# 01_Top.net
KiCad netlist of a schematic drawn in Altium Designer
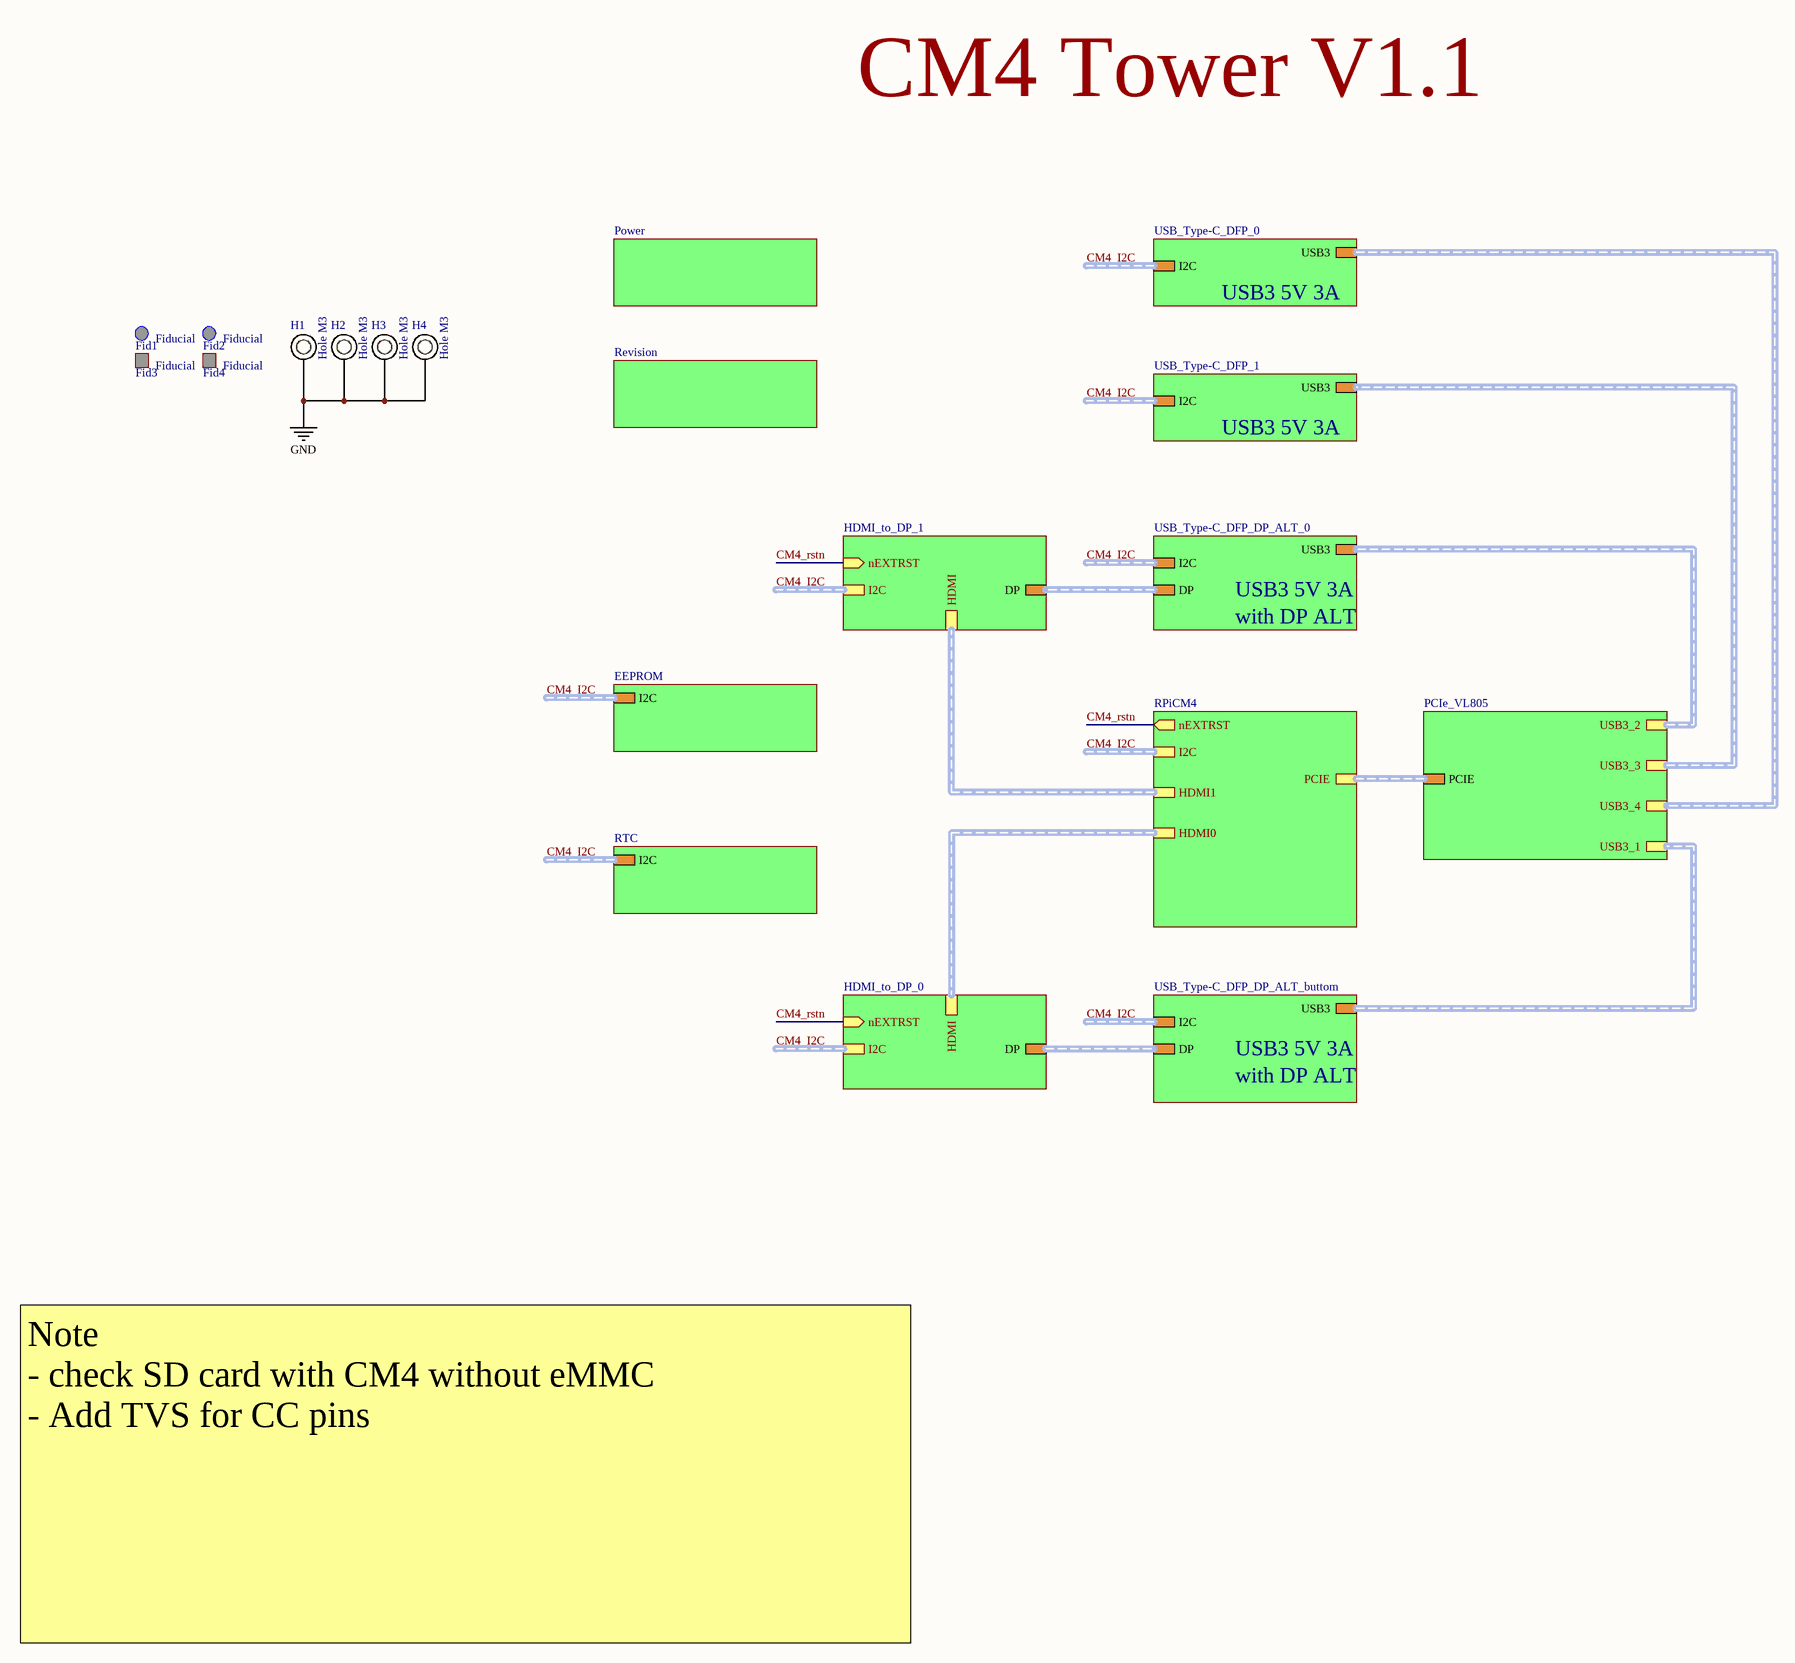
[diagram p0: 01_Top.SchDoc]

(export (version "E")
  (design (tool "Eeschema 10.0.6"))
  (components
    (comp (ref "Fid1")
      (value "Fiducial")
      (footprint "FidR_1.0mm")
      (description "Fiducial Round 1mm")
      (fields (field (name "REFVAL") "Fiducial") (field (name "PART NUMBER") "ME0011"))
      (libsource (lib "GTS_Database") (part "FidR_1.0mm"))
    )
    (comp (ref "Fid2")
      (value "Fiducial")
      (footprint "FidR_1.0mm")
      (description "Fiducial Round 1mm")
      (fields (field (name "REFVAL") "Fiducial") (field (name "PART NUMBER") "ME0011"))
      (libsource (lib "GTS_Database") (part "FidR_1.0mm"))
    )
    (comp (ref "Fid3")
      (value "Fiducial")
      (footprint "FidS_1.0mm")
      (description "Fiducial Sqaure 1mm")
      (fields (field (name "REFVAL") "Fiducial") (field (name "PART NUMBER") "ME0012"))
      (libsource (lib "GTS_Database") (part "FidS_1.0mm"))
    )
    (comp (ref "Fid4")
      (value "Fiducial")
      (footprint "FidS_1.0mm")
      (description "Fiducial Sqaure 1mm")
      (fields (field (name "REFVAL") "Fiducial") (field (name "PART NUMBER") "ME0012"))
      (libsource (lib "GTS_Database") (part "FidS_1.0mm"))
    )
    (comp (ref "H1")
      (value "Hole M3")
      (footprint "HOLE_M3")
      (description "Mounting Hole M3")
      (fields (field (name "REFVAL") "Hole M3") (field (name "PART NUMBER") "ME0001"))
      (libsource (lib "GTS_Database") (part "HOLE"))
    )
    (comp (ref "H2")
      (value "Hole M3")
      (footprint "HOLE_M3")
      (description "Mounting Hole M3")
      (fields (field (name "REFVAL") "Hole M3") (field (name "PART NUMBER") "ME0001"))
      (libsource (lib "GTS_Database") (part "HOLE"))
    )
    (comp (ref "H3")
      (value "Hole M3")
      (footprint "HOLE_M3")
      (description "Mounting Hole M3")
      (fields (field (name "REFVAL") "Hole M3") (field (name "PART NUMBER") "ME0001"))
      (libsource (lib "GTS_Database") (part "HOLE"))
    )
    (comp (ref "H4")
      (value "Hole M3")
      (footprint "HOLE_M3")
      (description "Mounting Hole M3")
      (fields (field (name "REFVAL") "Hole M3") (field (name "PART NUMBER") "ME0001"))
      (libsource (lib "GTS_Database") (part "HOLE"))
    )
  )
  (nets
    (net (code "13") (name "GND") (class "Default")
      (node (ref "H1") (pin "1") (pinfunction "1_1") (pintype "passive"))
      (node (ref "H2") (pin "1") (pinfunction "1_1") (pintype "passive"))
      (node (ref "H3") (pin "1") (pinfunction "1_1") (pintype "passive"))
      (node (ref "H4") (pin "1") (pinfunction "1_1") (pintype "passive"))
    )
  )
)
